# DRAIVER.net
KiCad netlist of a schematic drawn in EAGLE
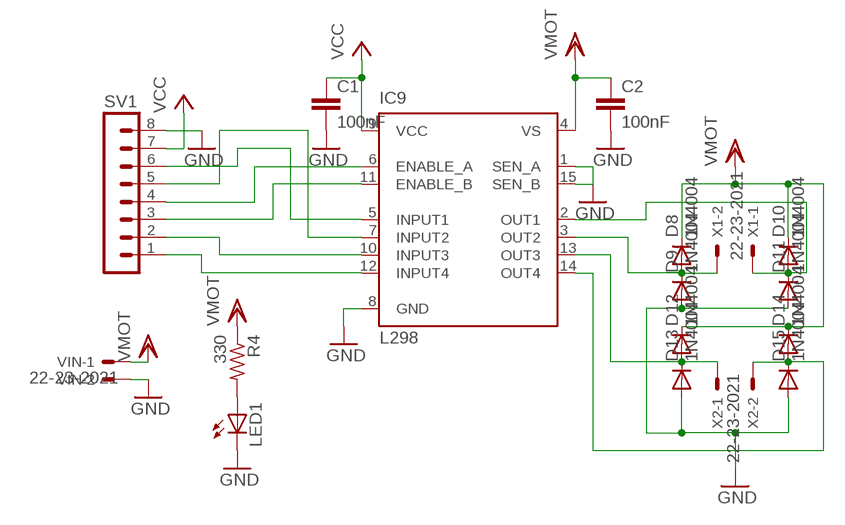
[diagram p0: schematic, sheet 1]

(export (version "E")
  (design (tool "Eeschema 10.0.6"))
  (components
    (comp (ref "C1")
      (value "100nF")
      (footprint "eagle-import:C025-025X050")
      (libsource (lib "eagle-import") (part "C-EU025-025X050"))
    )
    (comp (ref "C2")
      (value "100nF")
      (footprint "eagle-import:C025-025X050")
      (libsource (lib "eagle-import") (part "C-EU025-025X050"))
    )
    (comp (ref "D8")
      (value "1N4004")
      (footprint "eagle-import:DO41-10")
      (libsource (lib "eagle-import") (part "1N4004"))
    )
    (comp (ref "D9")
      (value "1N4004")
      (footprint "eagle-import:DO41-10")
      (libsource (lib "eagle-import") (part "1N4004"))
    )
    (comp (ref "D10")
      (value "1N4004")
      (footprint "eagle-import:DO41-10")
      (libsource (lib "eagle-import") (part "1N4004"))
    )
    (comp (ref "D11")
      (value "1N4004")
      (footprint "eagle-import:DO41-10")
      (libsource (lib "eagle-import") (part "1N4004"))
    )
    (comp (ref "D12")
      (value "1N4004")
      (footprint "eagle-import:DO41-10")
      (libsource (lib "eagle-import") (part "1N4004"))
    )
    (comp (ref "D13")
      (value "1N4004")
      (footprint "eagle-import:DO41-10")
      (libsource (lib "eagle-import") (part "1N4004"))
    )
    (comp (ref "D14")
      (value "1N4004")
      (footprint "eagle-import:DO41-10")
      (libsource (lib "eagle-import") (part "1N4004"))
    )
    (comp (ref "D15")
      (value "1N4004")
      (footprint "eagle-import:DO41-10")
      (libsource (lib "eagle-import") (part "1N4004"))
    )
    (comp (ref "IC9")
      (value "L298")
      (footprint "eagle-import:MULTIWATT-15")
      (libsource (lib "eagle-import") (part "L298"))
    )
    (comp (ref "LED1")
      (value "LED3MM")
      (footprint "eagle-import:LED3MM")
      (libsource (lib "eagle-import") (part "LED3MM"))
    )
    (comp (ref "R4")
      (value "330")
      (footprint "eagle-import:0207_10")
      (libsource (lib "eagle-import") (part "R-US_0207/10"))
    )
    (comp (ref "SV1")
      (value "MA08-1")
      (footprint "eagle-import:MA08-1")
      (libsource (lib "eagle-import") (part "MA08-1"))
    )
    (comp (ref "VIN")
      (value "22-23-2021")
      (footprint "eagle-import:22-23-2021")
      (fields
        (field (name "MF") "MOLEX")
        (field (name "MF_1") "MOLEX")
        (field (name "MPN") "22-23-2021")
        (field (name "OC_FARNELL") "1462926")
        (field (name "OC_NEWARK") "25C3832")
      )
      (libsource (lib "eagle-import") (part "22-23-2021"))
    )
    (comp (ref "X1")
      (value "22-23-2021")
      (footprint "eagle-import:22-23-2021")
      (fields (field (name "MF") "MOLEX"))
      (libsource (lib "eagle-import") (part "22-23-2021"))
    )
    (comp (ref "X2")
      (value "22-23-2021")
      (footprint "eagle-import:22-23-2021")
      (fields (field (name "MF") "MOLEX"))
      (libsource (lib "eagle-import") (part "22-23-2021"))
    )
  )
  (nets
    (net (code "1") (name "GND") (class "Default")
      (node (ref "C1") (pin "2") (pinfunction "2_2") (pintype "passive"))
      (node (ref "C2") (pin "2") (pinfunction "2_2") (pintype "passive"))
      (node (ref "D11") (pin "A") (pinfunction "A_A") (pintype "passive"))
      (node (ref "D13") (pin "A") (pinfunction "A_A") (pintype "passive"))
      (node (ref "D15") (pin "A") (pinfunction "A_A") (pintype "passive"))
      (node (ref "D9") (pin "A") (pinfunction "A_A") (pintype "passive"))
      (node (ref "IC9") (pin "1") (pinfunction "SEN_A_1") (pintype "input"))
      (node (ref "IC9") (pin "15") (pinfunction "SEN_B_15") (pintype "input"))
      (node (ref "IC9") (pin "8") (pinfunction "GND_8") (pintype "power_in"))
      (node (ref "LED1") (pin "K") (pinfunction "C_K") (pintype "passive"))
      (node (ref "SV1") (pin "8") (pinfunction "8_8") (pintype "passive"))
      (node (ref "VIN") (pin "2") (pinfunction "S_2") (pintype "passive"))
    )
    (net (code "2") (name "Net-(IC9-ENABLE_A)") (class "Default")
      (node (ref "IC9") (pin "6") (pinfunction "ENABLE_A_6") (pintype "input"))
      (node (ref "SV1") (pin "4") (pinfunction "4_4") (pintype "passive"))
    )
    (net (code "3") (name "Net-(IC9-ENABLE_B)") (class "Default")
      (node (ref "IC9") (pin "11") (pinfunction "ENABLE_B_11") (pintype "input"))
      (node (ref "SV1") (pin "3") (pinfunction "3_3") (pintype "passive"))
    )
    (net (code "4") (name "Net-(IC9-INPUT1)") (class "Default")
      (node (ref "IC9") (pin "5") (pinfunction "INPUT1_5") (pintype "input"))
      (node (ref "SV1") (pin "6") (pinfunction "6_6") (pintype "passive"))
    )
    (net (code "5") (name "Net-(IC9-INPUT2)") (class "Default")
      (node (ref "IC9") (pin "7") (pinfunction "INPUT2_7") (pintype "input"))
      (node (ref "SV1") (pin "5") (pinfunction "5_5") (pintype "passive"))
    )
    (net (code "6") (name "Net-(IC9-INPUT3)") (class "Default")
      (node (ref "IC9") (pin "10") (pinfunction "INPUT3_10") (pintype "input"))
      (node (ref "SV1") (pin "2") (pinfunction "2_2") (pintype "passive"))
    )
    (net (code "7") (name "Net-(IC9-INPUT4)") (class "Default")
      (node (ref "IC9") (pin "12") (pinfunction "INPUT4_12") (pintype "input"))
      (node (ref "SV1") (pin "1") (pinfunction "1_1") (pintype "passive"))
    )
    (net (code "8") (name "Net-(IC9-OUT1)") (class "Default")
      (node (ref "D10") (pin "A") (pinfunction "A_A") (pintype "passive"))
      (node (ref "D11") (pin "C") (pinfunction "C_C") (pintype "passive"))
      (node (ref "IC9") (pin "2") (pinfunction "OUT1_2") (pintype "output"))
      (node (ref "X1") (pin "1") (pinfunction "S_1") (pintype "passive"))
    )
    (net (code "9") (name "Net-(IC9-OUT2)") (class "Default")
      (node (ref "D8") (pin "A") (pinfunction "A_A") (pintype "passive"))
      (node (ref "D9") (pin "C") (pinfunction "C_C") (pintype "passive"))
      (node (ref "IC9") (pin "3") (pinfunction "OUT2_3") (pintype "output"))
      (node (ref "X1") (pin "2") (pinfunction "S_2") (pintype "passive"))
    )
    (net (code "10") (name "Net-(IC9-OUT3)") (class "Default")
      (node (ref "D12") (pin "A") (pinfunction "A_A") (pintype "passive"))
      (node (ref "D13") (pin "C") (pinfunction "C_C") (pintype "passive"))
      (node (ref "IC9") (pin "13") (pinfunction "OUT3_13") (pintype "output"))
      (node (ref "X2") (pin "1") (pinfunction "S_1") (pintype "passive"))
    )
    (net (code "11") (name "Net-(IC9-OUT4)") (class "Default")
      (node (ref "D14") (pin "A") (pinfunction "A_A") (pintype "passive"))
      (node (ref "D15") (pin "C") (pinfunction "C_C") (pintype "passive"))
      (node (ref "IC9") (pin "14") (pinfunction "OUT4_14") (pintype "output"))
      (node (ref "X2") (pin "2") (pinfunction "S_2") (pintype "passive"))
    )
    (net (code "12") (name "Net-(LED1-PadA)") (class "Default")
      (node (ref "LED1") (pin "A") (pinfunction "A_A") (pintype "passive"))
      (node (ref "R4") (pin "2") (pinfunction "2_2") (pintype "passive"))
    )
    (net (code "13") (name "VCC") (class "Default")
      (node (ref "C1") (pin "1") (pinfunction "1_1") (pintype "passive"))
      (node (ref "IC9") (pin "9") (pinfunction "VCC_9") (pintype "power_in"))
      (node (ref "SV1") (pin "7") (pinfunction "7_7") (pintype "passive"))
    )
    (net (code "14") (name "VMOT") (class "Default")
      (node (ref "C2") (pin "1") (pinfunction "1_1") (pintype "passive"))
      (node (ref "D10") (pin "C") (pinfunction "C_C") (pintype "passive"))
      (node (ref "D12") (pin "C") (pinfunction "C_C") (pintype "passive"))
      (node (ref "D14") (pin "C") (pinfunction "C_C") (pintype "passive"))
      (node (ref "D8") (pin "C") (pinfunction "C_C") (pintype "passive"))
      (node (ref "IC9") (pin "4") (pinfunction "VS_4") (pintype "power_in"))
      (node (ref "R4") (pin "1") (pinfunction "1_1") (pintype "passive"))
      (node (ref "VIN") (pin "1") (pinfunction "S_1") (pintype "passive"))
    )
  )
)
